# Zeus.net
KiCad netlist of a schematic drawn in EAGLE
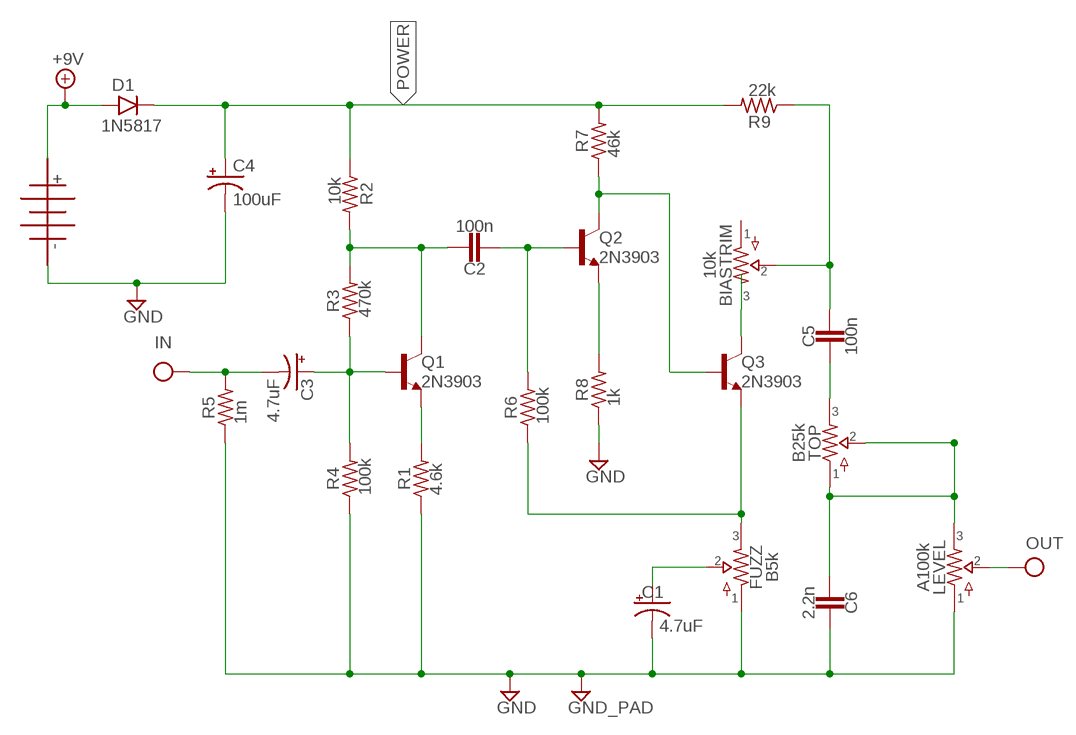
[diagram p0: schematic, sheet 1]

(export (version "E")
  (design (tool "Eeschema 10.0.6"))
  (components
    (comp (ref "9V")
      (value "BATTERYBAT2")
      (footprint "eagle-import:BATTERY2")
      (libsource (lib "eagle-import") (part "BATTERYBAT2"))
    )
    (comp (ref "BIASTRIM")
      (value "10k")
      (footprint "eagle-import:TRIM1")
      (libsource (lib "eagle-import") (part "TRIMMER"))
    )
    (comp (ref "C1")
      (value "4.7uF")
      (footprint "eagle-import:050_020_1")
      (libsource (lib "eagle-import") (part "0501"))
    )
    (comp (ref "C2")
      (value "100n")
      (footprint "eagle-import:0.2_.SML")
      (libsource (lib "eagle-import") (part "CAP.2"))
    )
    (comp (ref "C3")
      (value "4.7uF")
      (footprint "eagle-import:050_020_1")
      (libsource (lib "eagle-import") (part "0501"))
    )
    (comp (ref "C4")
      (value "100uF")
      (footprint "eagle-import:063_025")
      (libsource (lib "eagle-import") (part "0631"))
    )
    (comp (ref "C5")
      (value "100n")
      (footprint "eagle-import:0.2_.SML")
      (libsource (lib "eagle-import") (part "CAP.2"))
    )
    (comp (ref "C6")
      (value "2.2n")
      (footprint "eagle-import:0.2_.SML")
      (libsource (lib "eagle-import") (part "CAP.2"))
    )
    (comp (ref "D1")
      (value "1N5817")
      (footprint "eagle-import:DO41-3")
      (libsource (lib "eagle-import") (part "DO41.3"))
    )
    (comp (ref "FUZZ")
      (value "B5k")
      (footprint "eagle-import:16MM_B.MOUNT")
      (libsource (lib "eagle-import") (part "16MM.1"))
    )
    (comp (ref "GND")
      (value "GND_PAD")
      (footprint "eagle-import:SQUARE")
      (libsource (lib "eagle-import") (part "GND_PAD"))
    )
    (comp (ref "IN")
      (value "IN")
      (footprint "eagle-import:SQUARE")
      (libsource (lib "eagle-import") (part "IN"))
    )
    (comp (ref "LEVEL")
      (value "A100k")
      (footprint "eagle-import:16MM_B.MOUNT")
      (libsource (lib "eagle-import") (part "16MM.1"))
    )
    (comp (ref "OUT")
      (value "OUT")
      (footprint "eagle-import:SQUARE")
      (libsource (lib "eagle-import") (part "OUT"))
    )
    (comp (ref "Q1")
      (value "2N3903")
      (footprint "eagle-import:TO92")
      (libsource (lib "eagle-import") (part "2N5088"))
    )
    (comp (ref "Q2")
      (value "2N3903")
      (footprint "eagle-import:TO92")
      (libsource (lib "eagle-import") (part "2N5088"))
    )
    (comp (ref "Q3")
      (value "2N3903")
      (footprint "eagle-import:TO92")
      (libsource (lib "eagle-import") (part "2N5088"))
    )
    (comp (ref "R1")
      (value "4.6k")
      (footprint "eagle-import:R0207_3")
      (libsource (lib "eagle-import") (part "RESISTORS.3B"))
    )
    (comp (ref "R2")
      (value "10k")
      (footprint "eagle-import:R0207_3")
      (libsource (lib "eagle-import") (part "RESISTORS.3B"))
    )
    (comp (ref "R3")
      (value "470k")
      (footprint "eagle-import:R0207_3")
      (libsource (lib "eagle-import") (part "RESISTORS.3B"))
    )
    (comp (ref "R4")
      (value "100k")
      (footprint "eagle-import:R0207_3")
      (libsource (lib "eagle-import") (part "RESISTORS.3B"))
    )
    (comp (ref "R5")
      (value "1m")
      (footprint "eagle-import:R0207_3")
      (libsource (lib "eagle-import") (part "RESISTORS.3B"))
    )
    (comp (ref "R6")
      (value "100k")
      (footprint "eagle-import:R0207_3")
      (libsource (lib "eagle-import") (part "RESISTORS.3B"))
    )
    (comp (ref "R7")
      (value "46k")
      (footprint "eagle-import:R0207_3")
      (libsource (lib "eagle-import") (part "RESISTORS.3B"))
    )
    (comp (ref "R8")
      (value "1k")
      (footprint "eagle-import:R0207_3")
      (libsource (lib "eagle-import") (part "RESISTORS.3B"))
    )
    (comp (ref "R9")
      (value "22k")
      (footprint "eagle-import:R0207_3")
      (libsource (lib "eagle-import") (part "RESISTORS.3B"))
    )
    (comp (ref "TOP")
      (value "B25k")
      (footprint "eagle-import:16MM_B.MOUNT")
      (libsource (lib "eagle-import") (part "16MM.1"))
    )
  )
  (nets
    (net (code "1") (name "+9V") (class "Default")
      (node (ref "9V") (pin "P$1") (pinfunction "P$1_P$1") (pintype "bidirectional"))
      (node (ref "D1") (pin "A") (pinfunction "A_A") (pintype "passive"))
    )
    (net (code "2") (name "GND") (class "Default")
      (node (ref "9V") (pin "P$2") (pinfunction "P$2_P$2") (pintype "bidirectional"))
      (node (ref "C1") (pin "-") (pinfunction "-_-") (pintype "passive"))
      (node (ref "C4") (pin "-") (pinfunction "-_-") (pintype "passive"))
      (node (ref "C6") (pin "1") (pinfunction "1_1") (pintype "passive"))
      (node (ref "FUZZ") (pin "1") (pinfunction "1_1") (pintype "passive"))
      (node (ref "GND") (pin "1") (pinfunction "GND_1") (pintype "power_in"))
      (node (ref "LEVEL") (pin "1") (pinfunction "1_1") (pintype "passive"))
      (node (ref "R1") (pin "1") (pinfunction "1_1") (pintype "passive"))
      (node (ref "R4") (pin "1") (pinfunction "1_1") (pintype "passive"))
      (node (ref "R5") (pin "1") (pinfunction "1_1") (pintype "passive"))
      (node (ref "R8") (pin "1") (pinfunction "1_1") (pintype "passive"))
    )
    (net (code "3") (name "IN") (class "Default")
      (node (ref "C3") (pin "-") (pinfunction "-_-") (pintype "passive"))
      (node (ref "IN") (pin "1") (pinfunction "IN_1") (pintype "power_in"))
      (node (ref "R5") (pin "2") (pinfunction "2_2") (pintype "passive"))
    )
    (net (code "4") (name "Net-(BIASTRIM-Pad2)") (class "Default")
      (node (ref "BIASTRIM") (pin "2") (pinfunction "2_2") (pintype "passive"))
      (node (ref "C5") (pin "1") (pinfunction "1_1") (pintype "passive"))
      (node (ref "R9") (pin "1") (pinfunction "1_1") (pintype "passive"))
    )
    (net (code "5") (name "Net-(C1-Pad+)") (class "Default")
      (node (ref "C1") (pin "+") (pinfunction "+_+") (pintype "passive"))
      (node (ref "FUZZ") (pin "2") (pinfunction "2_2") (pintype "passive"))
    )
    (net (code "6") (name "Net-(C5-Pad2)") (class "Default")
      (node (ref "C5") (pin "2") (pinfunction "2_2") (pintype "passive"))
      (node (ref "TOP") (pin "3") (pinfunction "3_3") (pintype "passive"))
    )
    (net (code "7") (name "Net-(C6-Pad2)") (class "Default")
      (node (ref "C6") (pin "2") (pinfunction "2_2") (pintype "passive"))
      (node (ref "LEVEL") (pin "3") (pinfunction "3_3") (pintype "passive"))
      (node (ref "TOP") (pin "1") (pinfunction "1_1") (pintype "passive"))
      (node (ref "TOP") (pin "2") (pinfunction "2_2") (pintype "passive"))
    )
    (net (code "8") (name "Net-(Q1-B)") (class "Default")
      (node (ref "C3") (pin "+") (pinfunction "+_+") (pintype "passive"))
      (node (ref "Q1") (pin "2") (pinfunction "B_2") (pintype "passive"))
      (node (ref "R3") (pin "1") (pinfunction "1_1") (pintype "passive"))
      (node (ref "R4") (pin "2") (pinfunction "2_2") (pintype "passive"))
    )
    (net (code "9") (name "Net-(Q1-C)") (class "Default")
      (node (ref "C2") (pin "1") (pinfunction "1_1") (pintype "passive"))
      (node (ref "Q1") (pin "1") (pinfunction "C_1") (pintype "passive"))
      (node (ref "R2") (pin "2") (pinfunction "2_2") (pintype "passive"))
      (node (ref "R3") (pin "2") (pinfunction "2_2") (pintype "passive"))
    )
    (net (code "10") (name "Net-(Q1-E)") (class "Default")
      (node (ref "Q1") (pin "3") (pinfunction "E_3") (pintype "passive"))
      (node (ref "R1") (pin "2") (pinfunction "2_2") (pintype "passive"))
    )
    (net (code "11") (name "Net-(Q2-B)") (class "Default")
      (node (ref "C2") (pin "2") (pinfunction "2_2") (pintype "passive"))
      (node (ref "Q2") (pin "2") (pinfunction "B_2") (pintype "passive"))
      (node (ref "R6") (pin "2") (pinfunction "2_2") (pintype "passive"))
    )
    (net (code "12") (name "Net-(Q2-C)") (class "Default")
      (node (ref "Q2") (pin "1") (pinfunction "C_1") (pintype "passive"))
      (node (ref "Q3") (pin "2") (pinfunction "B_2") (pintype "passive"))
      (node (ref "R7") (pin "1") (pinfunction "1_1") (pintype "passive"))
    )
    (net (code "13") (name "Net-(Q2-E)") (class "Default")
      (node (ref "Q2") (pin "3") (pinfunction "E_3") (pintype "passive"))
      (node (ref "R8") (pin "2") (pinfunction "2_2") (pintype "passive"))
    )
    (net (code "14") (name "Net-(Q3-C)") (class "Default")
      (node (ref "BIASTRIM") (pin "3") (pinfunction "3_3") (pintype "passive"))
      (node (ref "Q3") (pin "1") (pinfunction "C_1") (pintype "passive"))
    )
    (net (code "15") (name "Net-(Q3-E)") (class "Default")
      (node (ref "FUZZ") (pin "3") (pinfunction "3_3") (pintype "passive"))
      (node (ref "Q3") (pin "3") (pinfunction "E_3") (pintype "passive"))
      (node (ref "R6") (pin "1") (pinfunction "1_1") (pintype "passive"))
    )
    (net (code "16") (name "OUT") (class "Default")
      (node (ref "LEVEL") (pin "2") (pinfunction "2_2") (pintype "passive"))
      (node (ref "OUT") (pin "1") (pinfunction "OUT_1") (pintype "power_in"))
    )
    (net (code "17") (name "POWER") (class "Default")
      (node (ref "C4") (pin "+") (pinfunction "+_+") (pintype "passive"))
      (node (ref "D1") (pin "C") (pinfunction "C_C") (pintype "passive"))
      (node (ref "R2") (pin "1") (pinfunction "1_1") (pintype "passive"))
      (node (ref "R7") (pin "2") (pinfunction "2_2") (pintype "passive"))
      (node (ref "R9") (pin "2") (pinfunction "2_2") (pintype "passive"))
    )
    (net (code "18") (name "unconnected-(BIASTRIM-Pad1)") (class "Default")
      (node (ref "BIASTRIM") (pin "1") (pinfunction "1_1") (pintype "passive"))
    )
  )
)
